# 1_P1.net
KiCad netlist of a schematic drawn in Altium Designer
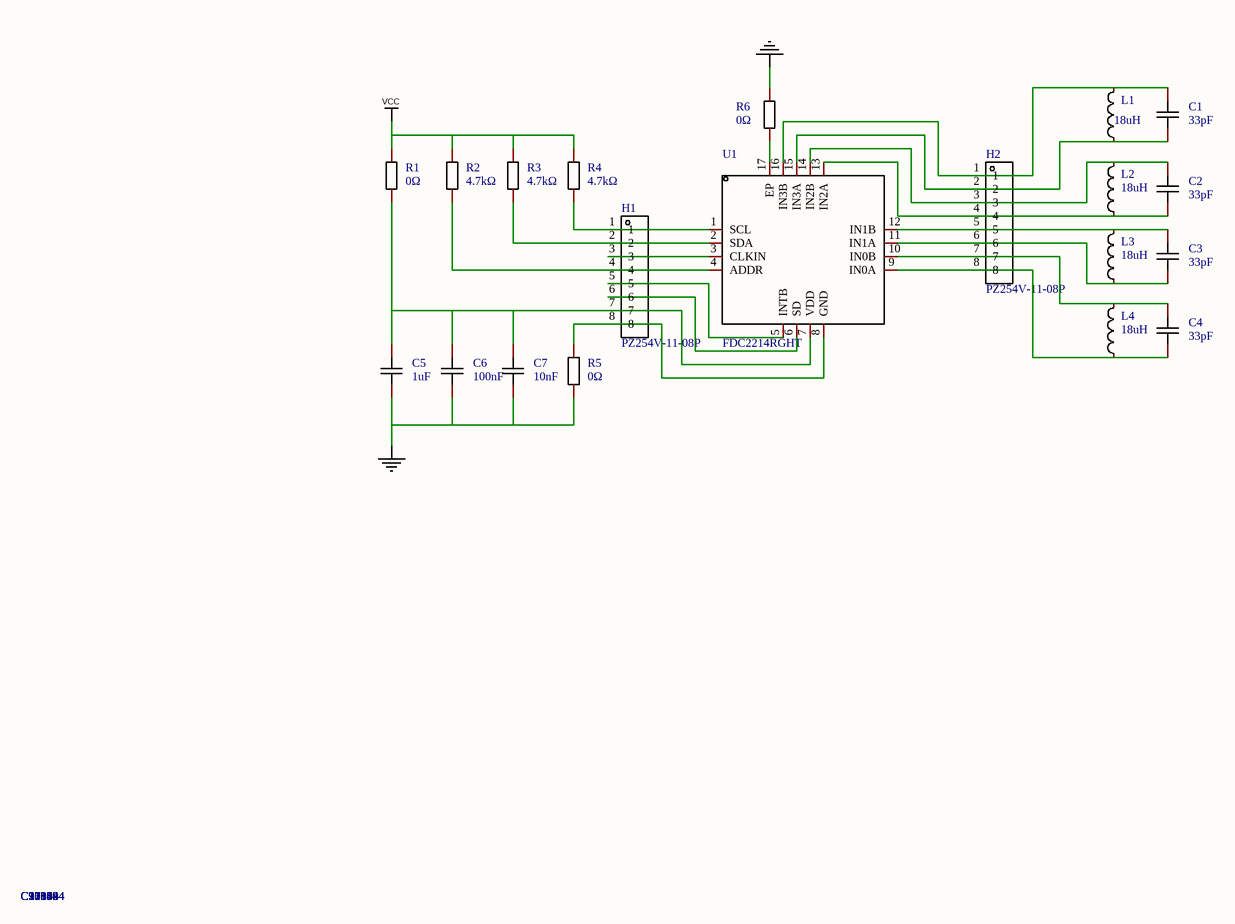
[diagram p0: 1_P1.schdoc]

(export (version "E")
  (design (tool "Eeschema 10.0.6"))
  (components
    (comp (ref "C1")
      (value "33pF")
      (description "容值:33pF;精度:±5%;额定电压:50V;材质(温度系数):C0G;")
      (fields
        (field (name "NAME") "33pF")
        (field (name "SUPPLIER PART") "C91368")
        (field (name "MANUFACTURER") "FH(风华)")
        (field (name "MANUFACTURER PART") "0603CG330J500NT")
      )
      (libsource (lib "altium-import") (part "root_1_0603CG330J500NT_"))
    )
    (comp (ref "C2")
      (value "33pF")
      (description "容值:33pF;精度:±5%;额定电压:50V;材质(温度系数):C0G;")
      (fields
        (field (name "NAME") "33pF")
        (field (name "SUPPLIER PART") "C91368")
        (field (name "MANUFACTURER") "FH(风华)")
        (field (name "MANUFACTURER PART") "0603CG330J500NT")
      )
      (libsource (lib "altium-import") (part "root_1_0603CG330J500NT_"))
    )
    (comp (ref "C3")
      (value "33pF")
      (description "容值:33pF;精度:±5%;额定电压:50V;材质(温度系数):C0G;")
      (fields
        (field (name "NAME") "33pF")
        (field (name "SUPPLIER PART") "C91368")
        (field (name "MANUFACTURER") "FH(风华)")
        (field (name "MANUFACTURER PART") "0603CG330J500NT")
      )
      (libsource (lib "altium-import") (part "root_1_0603CG330J500NT_"))
    )
    (comp (ref "C4")
      (value "33pF")
      (description "容值:33pF;精度:±5%;额定电压:50V;材质(温度系数):C0G;")
      (fields
        (field (name "NAME") "33pF")
        (field (name "SUPPLIER PART") "C91368")
        (field (name "MANUFACTURER") "FH(风华)")
        (field (name "MANUFACTURER PART") "0603CG330J500NT")
      )
      (libsource (lib "altium-import") (part "root_1_0603CG330J500NT_"))
    )
    (comp (ref "C5")
      (value "1uF")
      (description "容值:1uF;精度:±10%;额定电压:50V;材质(温度系数):X5R;")
      (fields
        (field (name "NAME") "1uF")
        (field (name "SUPPLIER PART") "C15849")
        (field (name "MANUFACTURER") "SAMSUNG(三星)")
        (field (name "MANUFACTURER PART") "CL10A105KB8NNNC")
      )
      (libsource (lib "altium-import") (part "root_1_CL10A105KB8NNNC_"))
    )
    (comp (ref "C6")
      (value "100nF")
      (description "容值:100nF;精度:±10%;额定电压:50V;材质(温度系数):X7R;")
      (fields
        (field (name "NAME") "100nF")
        (field (name "MANUFACTURER") "YAGEO(国巨)")
        (field (name "MANUFACTURER PART") "CC0603KRX7R9BB104")
      )
      (libsource (lib "altium-import") (part "root_1_CC0603KRX7R9BB104_"))
    )
    (comp (ref "C7")
      (value "10nF")
      (description "容值:10nF;精度:±10%;额定电压:50V;材质(温度系数):X7R;")
      (fields
        (field (name "NAME") "10nF")
        (field (name "SUPPLIER PART") "C57112")
        (field (name "MANUFACTURER") "FH(风华)")
        (field (name "MANUFACTURER PART") "0603B103K500NT")
      )
      (libsource (lib "altium-import") (part "root_1_0603B103K500NT_"))
    )
    (comp (ref "H1")
      (value "PZ254V-11-08P")
      (fields (field (name "NAME") "PZ254V-11-08P") (field (name "MANUFACTURER") "XFCN(兴飞)"))
      (libsource (lib "altium-import") (part "root_0_PZ254V-11-08P_"))
    )
    (comp (ref "H2")
      (value "PZ254V-11-08P")
      (fields (field (name "NAME") "PZ254V-11-08P") (field (name "MANUFACTURER") "XFCN(兴飞)"))
      (libsource (lib "altium-import") (part "root_0_PZ254V-11-08P_"))
    )
    (comp (ref "L1")
      (value "18uH")
      (description "电感值:18uH;精度:±10%;额定电流:1mA;饱和电流(Isat):-;直流电阻(DCR):1.85Ω;")
      (fields
        (field (name "NAME") "18uH")
        (field (name "SUPPLIER PART") "C57839")
        (field (name "MANUFACTURER") "Sunlord(顺络)")
        (field (name "MANUFACTURER PART") "SDFL1608T180KTF")
      )
      (libsource (lib "altium-import") (part "root_1_SDFL1608T180KTF_"))
    )
    (comp (ref "L2")
      (value "18uH")
      (description "电感值:18uH;精度:±10%;额定电流:1mA;饱和电流(Isat):-;直流电阻(DCR):1.85Ω;")
      (fields
        (field (name "NAME") "18uH")
        (field (name "SUPPLIER PART") "C57839")
        (field (name "MANUFACTURER") "Sunlord(顺络)")
        (field (name "MANUFACTURER PART") "SDFL1608T180KTF")
      )
      (libsource (lib "altium-import") (part "root_1_SDFL1608T180KTF_"))
    )
    (comp (ref "L3")
      (value "18uH")
      (description "电感值:18uH;精度:±10%;额定电流:1mA;饱和电流(Isat):-;直流电阻(DCR):1.85Ω;")
      (fields
        (field (name "NAME") "18uH")
        (field (name "SUPPLIER PART") "C57839")
        (field (name "MANUFACTURER") "Sunlord(顺络)")
        (field (name "MANUFACTURER PART") "SDFL1608T180KTF")
      )
      (libsource (lib "altium-import") (part "root_1_SDFL1608T180KTF_"))
    )
    (comp (ref "L4")
      (value "18uH")
      (description "电感值:18uH;精度:±10%;额定电流:1mA;饱和电流(Isat):-;直流电阻(DCR):1.85Ω;")
      (fields
        (field (name "NAME") "18uH")
        (field (name "SUPPLIER PART") "C57839")
        (field (name "MANUFACTURER") "Sunlord(顺络)")
        (field (name "MANUFACTURER PART") "SDFL1608T180KTF")
      )
      (libsource (lib "altium-import") (part "root_1_SDFL1608T180KTF_"))
    )
    (comp (ref "R1")
      (value "0Ω")
      (description "电阻类型:厚膜电阻;阻值:0Ω;精度:-;功率:100mW;")
      (fields
        (field (name "NAME") "0Ω")
        (field (name "SUPPLIER PART") "C100044")
        (field (name "MANUFACTURER") "YAGEO(国巨)")
        (field (name "MANUFACTURER PART") "RC0603FR-070RL")
      )
      (libsource (lib "altium-import") (part "root_1_RC0603FR-070RL_"))
    )
    (comp (ref "R2")
      (value "4.7kΩ")
      (description "电阻类型:厚膜电阻;阻值:4.7kΩ;精度:±1%;功率:100mW;")
      (fields
        (field (name "NAME") "4.7kΩ")
        (field (name "SUPPLIER PART") "C23162")
        (field (name "MANUFACTURER") "UNI-ROYAL(厚声)")
        (field (name "MANUFACTURER PART") "0603WAF4701T5E")
      )
      (libsource (lib "altium-import") (part "root_1_0603WAF4701T5E_"))
    )
    (comp (ref "R3")
      (value "4.7kΩ")
      (description "电阻类型:厚膜电阻;阻值:4.7kΩ;精度:±1%;功率:100mW;")
      (fields
        (field (name "NAME") "4.7kΩ")
        (field (name "SUPPLIER PART") "C23162")
        (field (name "MANUFACTURER") "UNI-ROYAL(厚声)")
        (field (name "MANUFACTURER PART") "0603WAF4701T5E")
      )
      (libsource (lib "altium-import") (part "root_1_0603WAF4701T5E_"))
    )
    (comp (ref "R4")
      (value "4.7kΩ")
      (description "电阻类型:厚膜电阻;阻值:4.7kΩ;精度:±1%;功率:100mW;")
      (fields
        (field (name "NAME") "4.7kΩ")
        (field (name "SUPPLIER PART") "C23162")
        (field (name "MANUFACTURER") "UNI-ROYAL(厚声)")
        (field (name "MANUFACTURER PART") "0603WAF4701T5E")
      )
      (libsource (lib "altium-import") (part "root_1_0603WAF4701T5E_"))
    )
    (comp (ref "R5")
      (value "0Ω")
      (description "电阻类型:厚膜电阻;阻值:0Ω;精度:-;功率:100mW;")
      (fields
        (field (name "NAME") "0Ω")
        (field (name "SUPPLIER PART") "C100044")
        (field (name "MANUFACTURER") "YAGEO(国巨)")
        (field (name "MANUFACTURER PART") "RC0603FR-070RL")
      )
      (libsource (lib "altium-import") (part "root_1_RC0603FR-070RL_"))
    )
    (comp (ref "R6")
      (value "0Ω")
      (description "电阻类型:厚膜电阻;阻值:0Ω;精度:-;功率:100mW;")
      (fields
        (field (name "NAME") "0Ω")
        (field (name "SUPPLIER PART") "C100044")
        (field (name "MANUFACTURER") "YAGEO(国巨)")
        (field (name "MANUFACTURER PART") "RC0603FR-070RL")
      )
      (libsource (lib "altium-import") (part "root_1_RC0603FR-070RL_"))
    )
    (comp (ref "U1")
      (value "FDC2214RGHT")
      (description "FDC2214 FDC2112 FDC2114")
      (fields (field (name "NAME") "FDC2214RGHT") (field (name "MANUFACTURER") "TI(德州仪器)"))
      (libsource (lib "altium-import") (part "root_0_FDC2214RGHT_"))
    )
  )
  (nets
    (net (code "1") (name "<NO NET>") (class "Default")
      (node (ref "C5") (pin "1") (pinfunction "1_1") (pintype "passive"))
      (node (ref "C6") (pin "1") (pinfunction "1_1") (pintype "passive"))
      (node (ref "C7") (pin "1") (pinfunction "1_1") (pintype "passive"))
      (node (ref "R5") (pin "1") (pinfunction "1_1") (pintype "passive"))
      (node (ref "R6") (pin "2") (pinfunction "2_2") (pintype "passive"))
    )
    (net (code "2") (name "Net-(U1-ADDR)") (class "Default")
      (node (ref "H1") (pin "4") (pinfunction "4_4") (pintype "passive"))
      (node (ref "R2") (pin "1") (pinfunction "1_1") (pintype "passive"))
      (node (ref "U1") (pin "4") (pinfunction "ADDR_4") (pintype "passive"))
    )
    (net (code "3") (name "Net-(U1-CLKIN)") (class "Default")
      (node (ref "H1") (pin "3") (pinfunction "3_3") (pintype "passive"))
      (node (ref "U1") (pin "3") (pinfunction "CLKIN_3") (pintype "passive"))
    )
    (net (code "4") (name "Net-(U1-EP)") (class "Default")
      (node (ref "R6") (pin "1") (pinfunction "1_1") (pintype "passive"))
      (node (ref "U1") (pin "17") (pinfunction "EP_17") (pintype "passive"))
    )
    (net (code "5") (name "Net-(U1-GND)") (class "Default")
      (node (ref "H1") (pin "8") (pinfunction "8_8") (pintype "passive"))
      (node (ref "R5") (pin "2") (pinfunction "2_2") (pintype "passive"))
      (node (ref "U1") (pin "8") (pinfunction "GND_8") (pintype "passive"))
    )
    (net (code "6") (name "Net-(U1-IN0A)") (class "Default")
      (node (ref "C4") (pin "1") (pinfunction "1_1") (pintype "passive"))
      (node (ref "H2") (pin "8") (pinfunction "8_8") (pintype "passive"))
      (node (ref "L4") (pin "1") (pinfunction "1_1") (pintype "passive"))
      (node (ref "U1") (pin "9") (pinfunction "IN0A_9") (pintype "passive"))
    )
    (net (code "7") (name "Net-(U1-IN0B)") (class "Default")
      (node (ref "C4") (pin "2") (pinfunction "2_2") (pintype "passive"))
      (node (ref "H2") (pin "7") (pinfunction "7_7") (pintype "passive"))
      (node (ref "L4") (pin "2") (pinfunction "2_2") (pintype "passive"))
      (node (ref "U1") (pin "10") (pinfunction "IN0B_10") (pintype "passive"))
    )
    (net (code "8") (name "Net-(U1-IN1A)") (class "Default")
      (node (ref "C3") (pin "1") (pinfunction "1_1") (pintype "passive"))
      (node (ref "H2") (pin "6") (pinfunction "6_6") (pintype "passive"))
      (node (ref "L3") (pin "1") (pinfunction "1_1") (pintype "passive"))
      (node (ref "U1") (pin "11") (pinfunction "IN1A_11") (pintype "passive"))
    )
    (net (code "9") (name "Net-(U1-IN1B)") (class "Default")
      (node (ref "C3") (pin "2") (pinfunction "2_2") (pintype "passive"))
      (node (ref "H2") (pin "5") (pinfunction "5_5") (pintype "passive"))
      (node (ref "L3") (pin "2") (pinfunction "2_2") (pintype "passive"))
      (node (ref "U1") (pin "12") (pinfunction "IN1B_12") (pintype "passive"))
    )
    (net (code "10") (name "Net-(U1-IN2A)") (class "Default")
      (node (ref "C2") (pin "1") (pinfunction "1_1") (pintype "passive"))
      (node (ref "H2") (pin "4") (pinfunction "4_4") (pintype "passive"))
      (node (ref "L2") (pin "1") (pinfunction "1_1") (pintype "passive"))
      (node (ref "U1") (pin "13") (pinfunction "IN2A_13") (pintype "passive"))
    )
    (net (code "11") (name "Net-(U1-IN2B)") (class "Default")
      (node (ref "C2") (pin "2") (pinfunction "2_2") (pintype "passive"))
      (node (ref "H2") (pin "3") (pinfunction "3_3") (pintype "passive"))
      (node (ref "L2") (pin "2") (pinfunction "2_2") (pintype "passive"))
      (node (ref "U1") (pin "14") (pinfunction "IN2B_14") (pintype "passive"))
    )
    (net (code "12") (name "Net-(U1-IN3A)") (class "Default")
      (node (ref "C1") (pin "1") (pinfunction "1_1") (pintype "passive"))
      (node (ref "H2") (pin "2") (pinfunction "2_2") (pintype "passive"))
      (node (ref "L1") (pin "1") (pinfunction "1_1") (pintype "passive"))
      (node (ref "U1") (pin "15") (pinfunction "IN3A_15") (pintype "passive"))
    )
    (net (code "13") (name "Net-(U1-IN3B)") (class "Default")
      (node (ref "C1") (pin "2") (pinfunction "2_2") (pintype "passive"))
      (node (ref "H2") (pin "1") (pinfunction "1_1") (pintype "passive"))
      (node (ref "L1") (pin "2") (pinfunction "2_2") (pintype "passive"))
      (node (ref "U1") (pin "16") (pinfunction "IN3B_16") (pintype "passive"))
    )
    (net (code "14") (name "Net-(U1-INTB)") (class "Default")
      (node (ref "H1") (pin "5") (pinfunction "5_5") (pintype "passive"))
      (node (ref "U1") (pin "5") (pinfunction "INTB_5") (pintype "passive"))
    )
    (net (code "15") (name "Net-(U1-SCL)") (class "Default")
      (node (ref "H1") (pin "1") (pinfunction "1_1") (pintype "passive"))
      (node (ref "R4") (pin "1") (pinfunction "1_1") (pintype "passive"))
      (node (ref "U1") (pin "1") (pinfunction "SCL_1") (pintype "passive"))
    )
    (net (code "16") (name "Net-(U1-SD)") (class "Default")
      (node (ref "H1") (pin "6") (pinfunction "6_6") (pintype "passive"))
      (node (ref "U1") (pin "6") (pinfunction "SD_6") (pintype "passive"))
    )
    (net (code "17") (name "Net-(U1-SDA)") (class "Default")
      (node (ref "H1") (pin "2") (pinfunction "2_2") (pintype "passive"))
      (node (ref "R3") (pin "1") (pinfunction "1_1") (pintype "passive"))
      (node (ref "U1") (pin "2") (pinfunction "SDA_2") (pintype "passive"))
    )
    (net (code "18") (name "Net-(U1-VDD)") (class "Default")
      (node (ref "C5") (pin "2") (pinfunction "2_2") (pintype "passive"))
      (node (ref "C6") (pin "2") (pinfunction "2_2") (pintype "passive"))
      (node (ref "C7") (pin "2") (pinfunction "2_2") (pintype "passive"))
      (node (ref "H1") (pin "7") (pinfunction "7_7") (pintype "passive"))
      (node (ref "R1") (pin "1") (pinfunction "1_1") (pintype "passive"))
      (node (ref "U1") (pin "7") (pinfunction "VDD_7") (pintype "passive"))
    )
    (net (code "19") (name "VCC") (class "Default")
      (node (ref "R1") (pin "2") (pinfunction "2_2") (pintype "passive"))
      (node (ref "R2") (pin "2") (pinfunction "2_2") (pintype "passive"))
      (node (ref "R3") (pin "2") (pinfunction "2_2") (pintype "passive"))
      (node (ref "R4") (pin "2") (pinfunction "2_2") (pintype "passive"))
    )
  )
)
